# INPUT.net
KiCad netlist of a schematic drawn in EAGLE
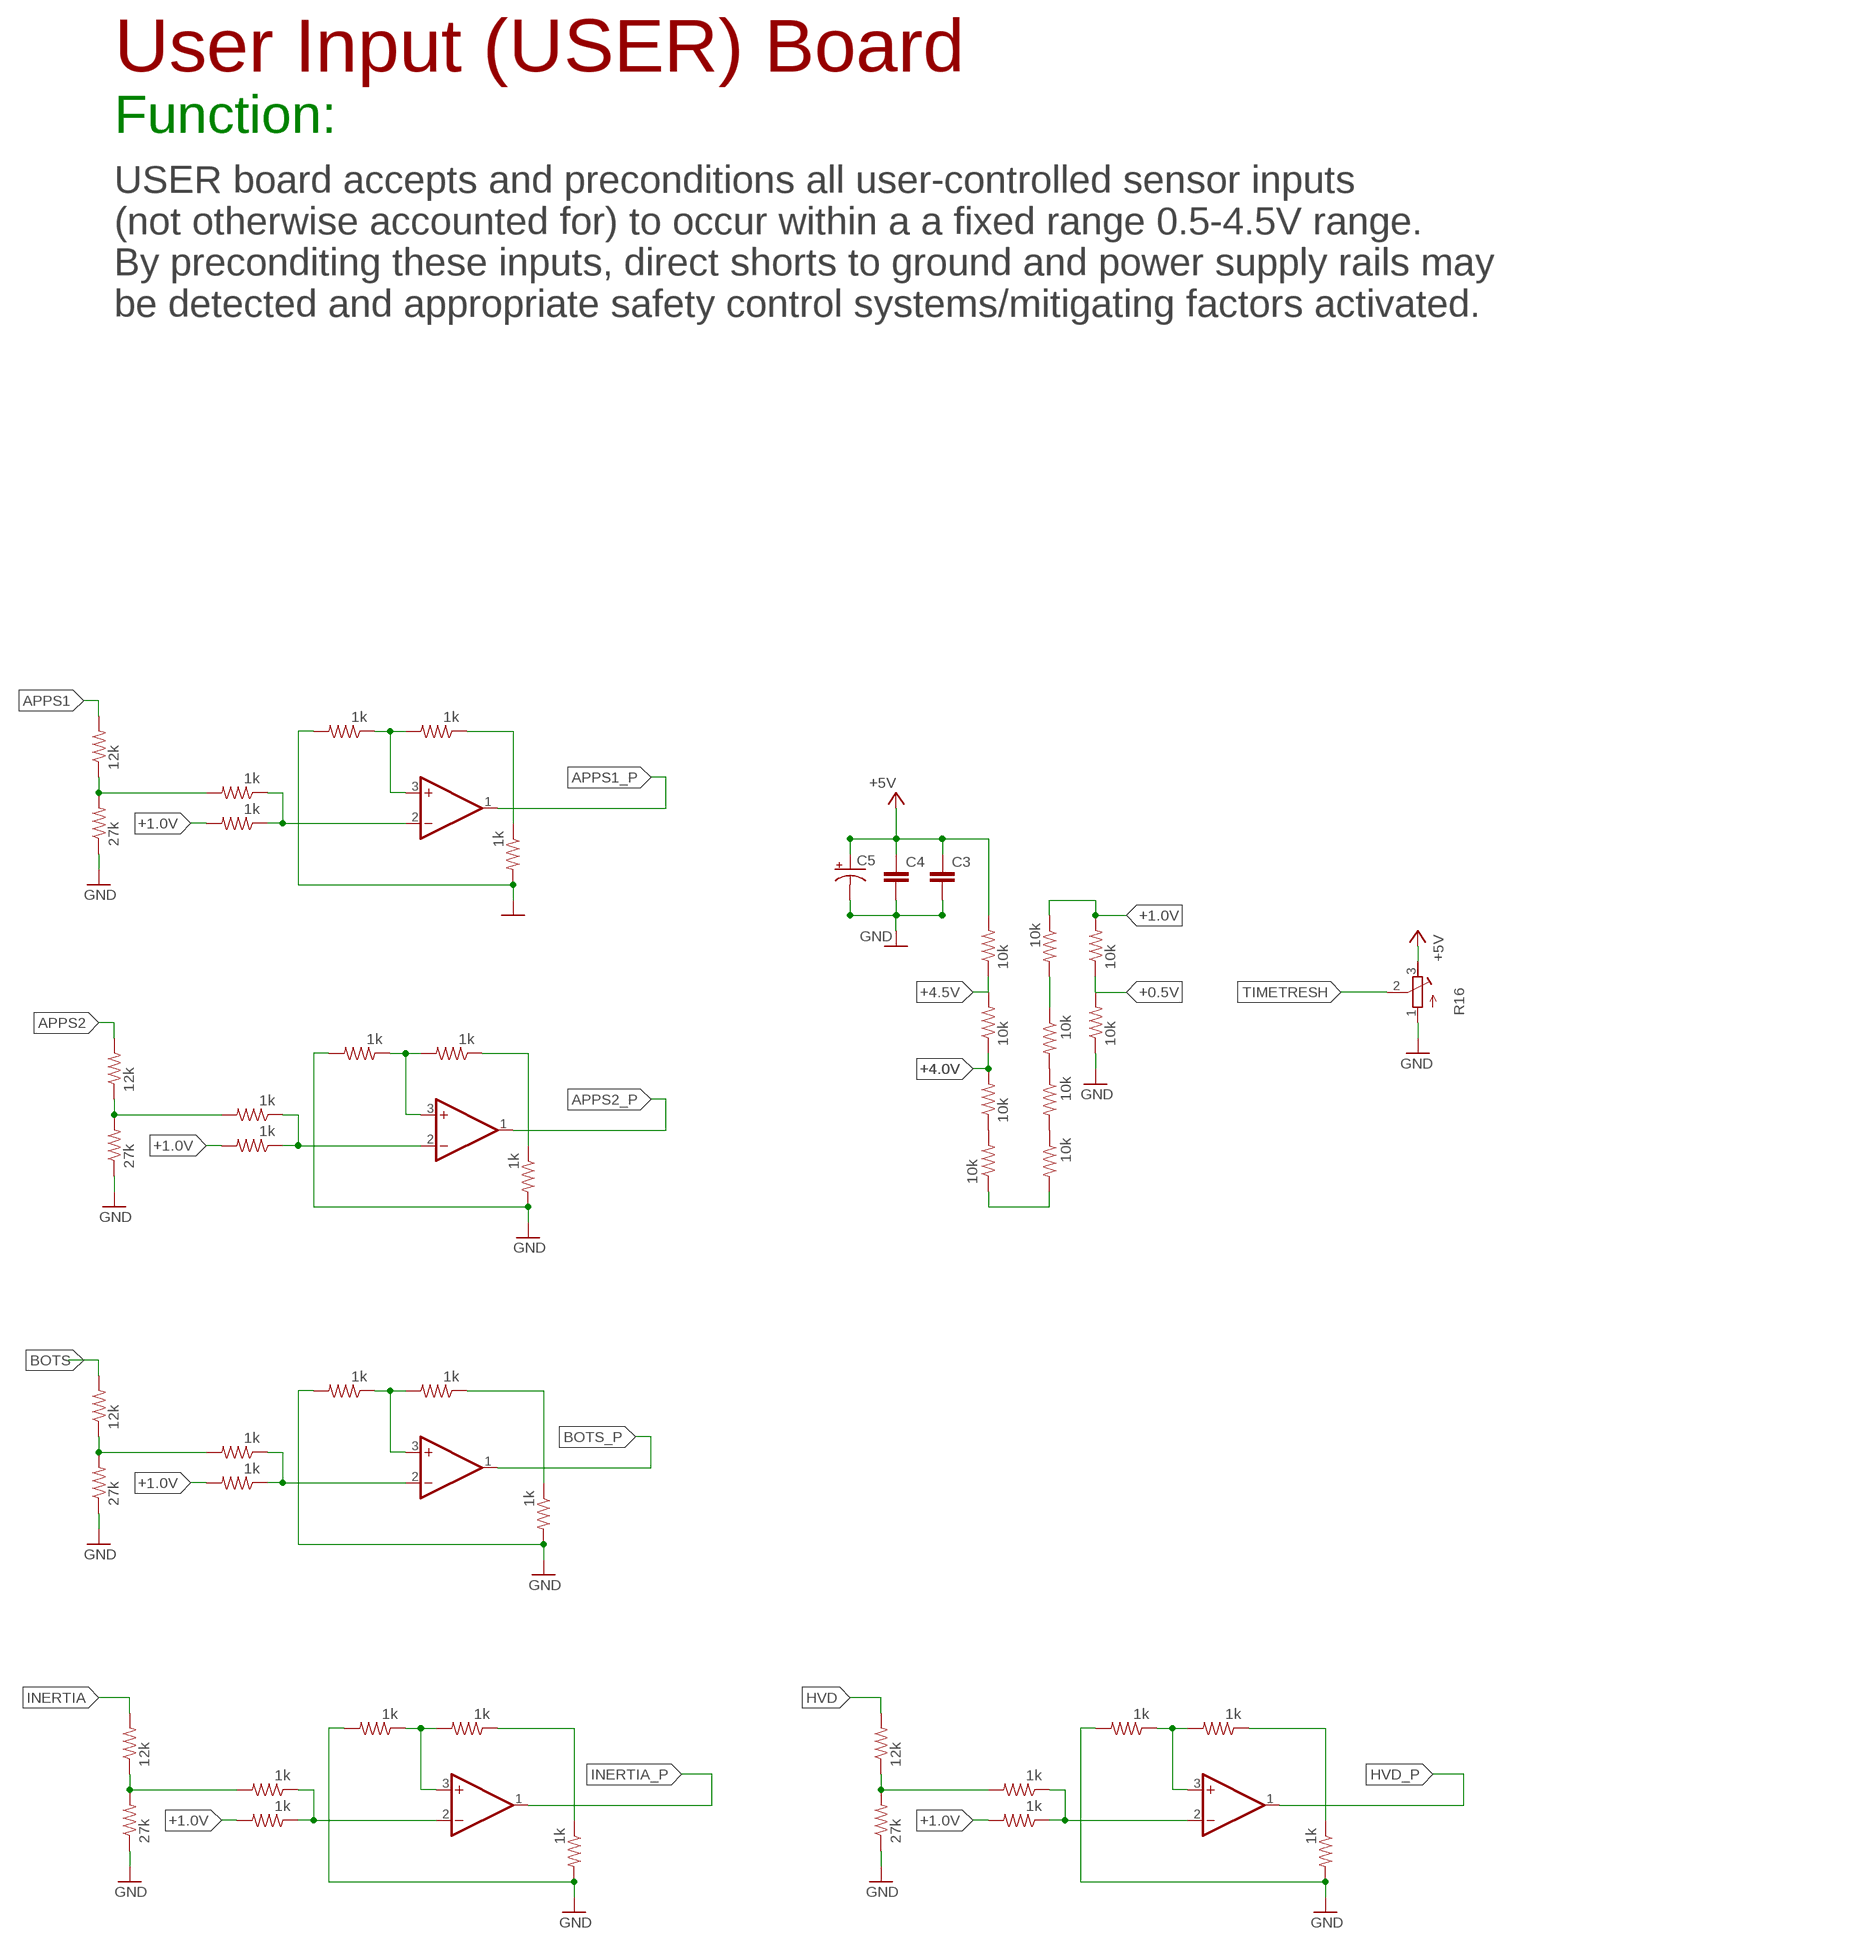
[diagram p0: schematic, sheet 1, part 1 of 2]
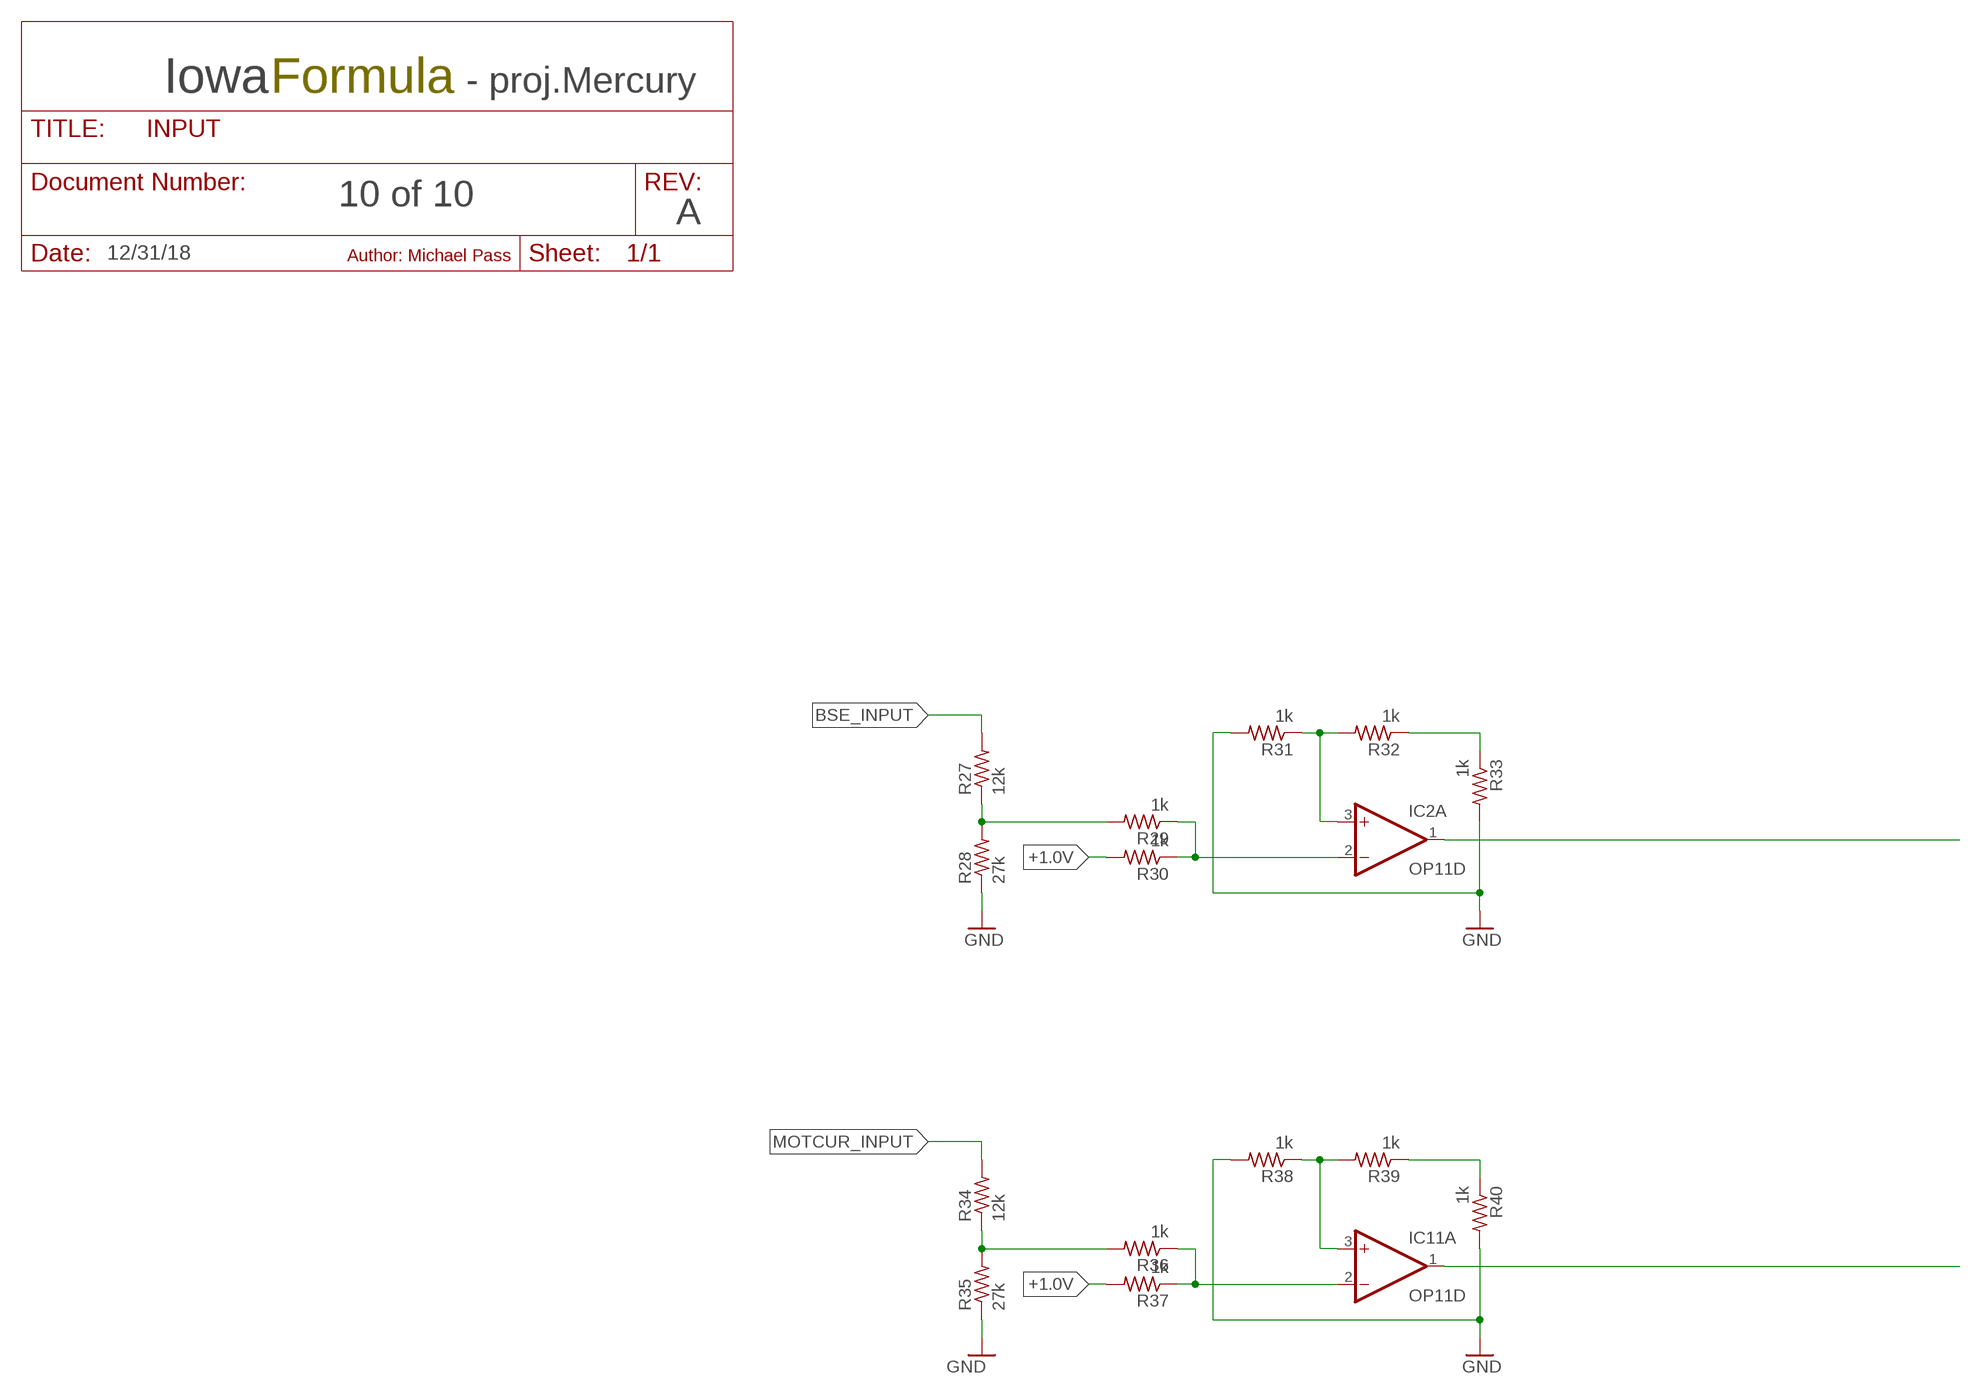
[diagram p1: schematic, sheet 1, part 2 of 2]

(export (version "E")
  (design (tool "Eeschema 10.0.6"))
  (components
    (comp (ref "C3")
      (value "C-EUC0805")
      (footprint "eagle-import:C0805")
      (libsource (lib "eagle-import") (part "C-EUC0805"))
    )
    (comp (ref "C4")
      (value "C-EUC0805")
      (footprint "eagle-import:C0805")
      (libsource (lib "eagle-import") (part "C-EUC0805"))
    )
    (comp (ref "C5")
      (value "CPOL-US085CS-1AR")
      (footprint "eagle-import:085CS_1AR")
      (libsource (lib "eagle-import") (part "CPOL-US085CS-1AR"))
    )
    (comp (ref "IC2")
      (value "OP11D")
      (footprint "eagle-import:SO14")
      (libsource (lib "eagle-import") (part "OP11D"))
    )
    (comp (ref "IC3")
      (value "OP11D")
      (footprint "eagle-import:SO14")
      (libsource (lib "eagle-import") (part "OP11D"))
    )
    (comp (ref "IC7")
      (value "OP11D")
      (footprint "eagle-import:SO14")
      (libsource (lib "eagle-import") (part "OP11D"))
    )
    (comp (ref "IC8")
      (value "OP11D")
      (footprint "eagle-import:SO14")
      (libsource (lib "eagle-import") (part "OP11D"))
    )
    (comp (ref "IC11")
      (value "OP11D")
      (footprint "eagle-import:SO14")
      (libsource (lib "eagle-import") (part "OP11D"))
    )
    (comp (ref "IC19")
      (value "OP11D")
      (footprint "eagle-import:SO14")
      (libsource (lib "eagle-import") (part "OP11D"))
    )
    (comp (ref "IC20")
      (value "OP11D")
      (footprint "eagle-import:SO14")
      (libsource (lib "eagle-import") (part "OP11D"))
    )
    (comp (ref "R1")
      (value "12k")
      (footprint "eagle-import:R0805")
      (libsource (lib "eagle-import") (part "R-US_R0805"))
    )
    (comp (ref "R2")
      (value "27k")
      (footprint "eagle-import:R0805")
      (libsource (lib "eagle-import") (part "R-US_R0805"))
    )
    (comp (ref "R5")
      (value "10k")
      (footprint "eagle-import:R0805")
      (libsource (lib "eagle-import") (part "R-US_R0805"))
    )
    (comp (ref "R6")
      (value "10k")
      (footprint "eagle-import:R0805")
      (libsource (lib "eagle-import") (part "R-US_R0805"))
    )
    (comp (ref "R7")
      (value "12k")
      (footprint "eagle-import:R0805")
      (libsource (lib "eagle-import") (part "R-US_R0805"))
    )
    (comp (ref "R8")
      (value "10k")
      (footprint "eagle-import:R0805")
      (libsource (lib "eagle-import") (part "R-US_R0805"))
    )
    (comp (ref "R9")
      (value "10k")
      (footprint "eagle-import:R0805")
      (libsource (lib "eagle-import") (part "R-US_R0805"))
    )
    (comp (ref "R10")
      (value "10k")
      (footprint "eagle-import:R0805")
      (libsource (lib "eagle-import") (part "R-US_R0805"))
    )
    (comp (ref "R11")
      (value "10k")
      (footprint "eagle-import:R0805")
      (libsource (lib "eagle-import") (part "R-US_R0805"))
    )
    (comp (ref "R12")
      (value "10k")
      (footprint "eagle-import:R0805")
      (libsource (lib "eagle-import") (part "R-US_R0805"))
    )
    (comp (ref "R13")
      (value "10k")
      (footprint "eagle-import:R0805")
      (libsource (lib "eagle-import") (part "R-US_R0805"))
    )
    (comp (ref "R14")
      (value "10k")
      (footprint "eagle-import:R0805")
      (libsource (lib "eagle-import") (part "R-US_R0805"))
    )
    (comp (ref "R15")
      (value "10k")
      (footprint "eagle-import:R0805")
      (libsource (lib "eagle-import") (part "R-US_R0805"))
    )
    (comp (ref "R16")
      (value "R-TRIMM3224X")
      (footprint "eagle-import:RTRIM3224X")
      (libsource (lib "eagle-import") (part "R-TRIMM3224X"))
    )
    (comp (ref "R21")
      (value "27k")
      (footprint "eagle-import:R0805")
      (libsource (lib "eagle-import") (part "R-US_R0805"))
    )
    (comp (ref "R22")
      (value "1k")
      (footprint "eagle-import:R0805")
      (libsource (lib "eagle-import") (part "R-US_R0805"))
    )
    (comp (ref "R23")
      (value "1k")
      (footprint "eagle-import:R0805")
      (libsource (lib "eagle-import") (part "R-US_R0805"))
    )
    (comp (ref "R24")
      (value "1k")
      (footprint "eagle-import:R0805")
      (libsource (lib "eagle-import") (part "R-US_R0805"))
    )
    (comp (ref "R25")
      (value "1k")
      (footprint "eagle-import:R0805")
      (libsource (lib "eagle-import") (part "R-US_R0805"))
    )
    (comp (ref "R26")
      (value "1k")
      (footprint "eagle-import:R0805")
      (libsource (lib "eagle-import") (part "R-US_R0805"))
    )
    (comp (ref "R27")
      (value "12k")
      (footprint "eagle-import:R0805")
      (libsource (lib "eagle-import") (part "R-US_R0805"))
    )
    (comp (ref "R28")
      (value "27k")
      (footprint "eagle-import:R0805")
      (libsource (lib "eagle-import") (part "R-US_R0805"))
    )
    (comp (ref "R29")
      (value "1k")
      (footprint "eagle-import:R0805")
      (libsource (lib "eagle-import") (part "R-US_R0805"))
    )
    (comp (ref "R30")
      (value "1k")
      (footprint "eagle-import:R0805")
      (libsource (lib "eagle-import") (part "R-US_R0805"))
    )
    (comp (ref "R31")
      (value "1k")
      (footprint "eagle-import:R0805")
      (libsource (lib "eagle-import") (part "R-US_R0805"))
    )
    (comp (ref "R32")
      (value "1k")
      (footprint "eagle-import:R0805")
      (libsource (lib "eagle-import") (part "R-US_R0805"))
    )
    (comp (ref "R33")
      (value "1k")
      (footprint "eagle-import:R0805")
      (libsource (lib "eagle-import") (part "R-US_R0805"))
    )
    (comp (ref "R34")
      (value "12k")
      (footprint "eagle-import:R0805")
      (libsource (lib "eagle-import") (part "R-US_R0805"))
    )
    (comp (ref "R35")
      (value "27k")
      (footprint "eagle-import:R0805")
      (libsource (lib "eagle-import") (part "R-US_R0805"))
    )
    (comp (ref "R36")
      (value "1k")
      (footprint "eagle-import:R0805")
      (libsource (lib "eagle-import") (part "R-US_R0805"))
    )
    (comp (ref "R37")
      (value "1k")
      (footprint "eagle-import:R0805")
      (libsource (lib "eagle-import") (part "R-US_R0805"))
    )
    (comp (ref "R38")
      (value "1k")
      (footprint "eagle-import:R0805")
      (libsource (lib "eagle-import") (part "R-US_R0805"))
    )
    (comp (ref "R39")
      (value "1k")
      (footprint "eagle-import:R0805")
      (libsource (lib "eagle-import") (part "R-US_R0805"))
    )
    (comp (ref "R40")
      (value "1k")
      (footprint "eagle-import:R0805")
      (libsource (lib "eagle-import") (part "R-US_R0805"))
    )
    (comp (ref "R66")
      (value "1k")
      (footprint "eagle-import:R0805")
      (libsource (lib "eagle-import") (part "R-US_R0805"))
    )
    (comp (ref "R67")
      (value "1k")
      (footprint "eagle-import:R0805")
      (libsource (lib "eagle-import") (part "R-US_R0805"))
    )
    (comp (ref "R68")
      (value "1k")
      (footprint "eagle-import:R0805")
      (libsource (lib "eagle-import") (part "R-US_R0805"))
    )
    (comp (ref "R69")
      (value "1k")
      (footprint "eagle-import:R0805")
      (libsource (lib "eagle-import") (part "R-US_R0805"))
    )
    (comp (ref "R70")
      (value "1k")
      (footprint "eagle-import:R0805")
      (libsource (lib "eagle-import") (part "R-US_R0805"))
    )
    (comp (ref "R71")
      (value "12k")
      (footprint "eagle-import:R0805")
      (libsource (lib "eagle-import") (part "R-US_R0805"))
    )
    (comp (ref "R72")
      (value "27k")
      (footprint "eagle-import:R0805")
      (libsource (lib "eagle-import") (part "R-US_R0805"))
    )
    (comp (ref "R73")
      (value "1k")
      (footprint "eagle-import:R0805")
      (libsource (lib "eagle-import") (part "R-US_R0805"))
    )
    (comp (ref "R74")
      (value "1k")
      (footprint "eagle-import:R0805")
      (libsource (lib "eagle-import") (part "R-US_R0805"))
    )
    (comp (ref "R75")
      (value "1k")
      (footprint "eagle-import:R0805")
      (libsource (lib "eagle-import") (part "R-US_R0805"))
    )
    (comp (ref "R76")
      (value "1k")
      (footprint "eagle-import:R0805")
      (libsource (lib "eagle-import") (part "R-US_R0805"))
    )
    (comp (ref "R77")
      (value "1k")
      (footprint "eagle-import:R0805")
      (libsource (lib "eagle-import") (part "R-US_R0805"))
    )
    (comp (ref "R78")
      (value "12k")
      (footprint "eagle-import:R0805")
      (libsource (lib "eagle-import") (part "R-US_R0805"))
    )
    (comp (ref "R79")
      (value "27k")
      (footprint "eagle-import:R0805")
      (libsource (lib "eagle-import") (part "R-US_R0805"))
    )
    (comp (ref "R80")
      (value "1k")
      (footprint "eagle-import:R0805")
      (libsource (lib "eagle-import") (part "R-US_R0805"))
    )
    (comp (ref "R81")
      (value "1k")
      (footprint "eagle-import:R0805")
      (libsource (lib "eagle-import") (part "R-US_R0805"))
    )
    (comp (ref "R82")
      (value "1k")
      (footprint "eagle-import:R0805")
      (libsource (lib "eagle-import") (part "R-US_R0805"))
    )
    (comp (ref "R83")
      (value "1k")
      (footprint "eagle-import:R0805")
      (libsource (lib "eagle-import") (part "R-US_R0805"))
    )
    (comp (ref "R84")
      (value "1k")
      (footprint "eagle-import:R0805")
      (libsource (lib "eagle-import") (part "R-US_R0805"))
    )
    (comp (ref "R85")
      (value "12k")
      (footprint "eagle-import:R0805")
      (libsource (lib "eagle-import") (part "R-US_R0805"))
    )
    (comp (ref "R86")
      (value "27k")
      (footprint "eagle-import:R0805")
      (libsource (lib "eagle-import") (part "R-US_R0805"))
    )
    (comp (ref "R87")
      (value "1k")
      (footprint "eagle-import:R0805")
      (libsource (lib "eagle-import") (part "R-US_R0805"))
    )
    (comp (ref "R88")
      (value "1k")
      (footprint "eagle-import:R0805")
      (libsource (lib "eagle-import") (part "R-US_R0805"))
    )
    (comp (ref "R89")
      (value "1k")
      (footprint "eagle-import:R0805")
      (libsource (lib "eagle-import") (part "R-US_R0805"))
    )
    (comp (ref "R90")
      (value "1k")
      (footprint "eagle-import:R0805")
      (libsource (lib "eagle-import") (part "R-US_R0805"))
    )
    (comp (ref "R91")
      (value "1k")
      (footprint "eagle-import:R0805")
      (libsource (lib "eagle-import") (part "R-US_R0805"))
    )
  )
  (nets
    (net (code "1") (name "+0.5V") (class "Default")
      (node (ref "R14") (pin "1") (pinfunction "1_1") (pintype "passive"))
      (node (ref "R15") (pin "2") (pinfunction "2_2") (pintype "passive"))
    )
    (net (code "2") (name "+1.0V") (class "Default")
      (node (ref "R13") (pin "1") (pinfunction "1_1") (pintype "passive"))
      (node (ref "R14") (pin "2") (pinfunction "2_2") (pintype "passive"))
      (node (ref "R23") (pin "2") (pinfunction "2_2") (pintype "passive"))
      (node (ref "R30") (pin "2") (pinfunction "2_2") (pintype "passive"))
      (node (ref "R37") (pin "2") (pinfunction "2_2") (pintype "passive"))
      (node (ref "R67") (pin "2") (pinfunction "2_2") (pintype "passive"))
      (node (ref "R74") (pin "2") (pinfunction "2_2") (pintype "passive"))
      (node (ref "R81") (pin "2") (pinfunction "2_2") (pintype "passive"))
      (node (ref "R88") (pin "2") (pinfunction "2_2") (pintype "passive"))
    )
    (net (code "3") (name "+4.0V") (class "Default")
      (node (ref "R6") (pin "1") (pinfunction "1_1") (pintype "passive"))
      (node (ref "R8") (pin "2") (pinfunction "2_2") (pintype "passive"))
    )
    (net (code "4") (name "+4.5V") (class "Default")
      (node (ref "R5") (pin "1") (pinfunction "1_1") (pintype "passive"))
      (node (ref "R6") (pin "2") (pinfunction "2_2") (pintype "passive"))
    )
    (net (code "5") (name "+5V") (class "Default")
      (node (ref "C3") (pin "1") (pinfunction "1_1") (pintype "passive"))
      (node (ref "C4") (pin "1") (pinfunction "1_1") (pintype "passive"))
      (node (ref "C5") (pin "+") (pinfunction "+_+") (pintype "passive"))
      (node (ref "R16") (pin "3") (pinfunction "E_3") (pintype "passive"))
      (node (ref "R5") (pin "2") (pinfunction "2_2") (pintype "passive"))
    )
    (net (code "6") (name "APPS1") (class "Default")
      (node (ref "R71") (pin "2") (pinfunction "2_2") (pintype "passive"))
    )
    (net (code "7") (name "APPS1_P") (class "Default")
      (node (ref "IC7") (pin "1") (pinfunction "OUT_1") (pintype "output"))
    )
    (net (code "8") (name "APPS2") (class "Default")
      (node (ref "R78") (pin "2") (pinfunction "2_2") (pintype "passive"))
    )
    (net (code "9") (name "APPS2_P") (class "Default")
      (node (ref "IC19") (pin "1") (pinfunction "OUT_1") (pintype "output"))
    )
    (net (code "10") (name "BOTS") (class "Default")
      (node (ref "R7") (pin "2") (pinfunction "2_2") (pintype "passive"))
    )
    (net (code "11") (name "BOTS_P") (class "Default")
      (node (ref "IC8") (pin "1") (pinfunction "OUT_1") (pintype "output"))
    )
    (net (code "12") (name "BSE_INPUT") (class "Default")
      (node (ref "R27") (pin "2") (pinfunction "2_2") (pintype "passive"))
    )
    (net (code "13") (name "GND") (class "Default")
      (node (ref "C3") (pin "2") (pinfunction "2_2") (pintype "passive"))
      (node (ref "C4") (pin "2") (pinfunction "2_2") (pintype "passive"))
      (node (ref "C5") (pin "-") (pinfunction "-_-") (pintype "passive"))
      (node (ref "R15") (pin "1") (pinfunction "1_1") (pintype "passive"))
      (node (ref "R16") (pin "1") (pinfunction "A_1") (pintype "passive"))
      (node (ref "R2") (pin "1") (pinfunction "1_1") (pintype "passive"))
      (node (ref "R21") (pin "1") (pinfunction "1_1") (pintype "passive"))
      (node (ref "R24") (pin "2") (pinfunction "2_2") (pintype "passive"))
      (node (ref "R26") (pin "2") (pinfunction "2_2") (pintype "passive"))
      (node (ref "R28") (pin "1") (pinfunction "1_1") (pintype "passive"))
      (node (ref "R31") (pin "2") (pinfunction "2_2") (pintype "passive"))
      (node (ref "R33") (pin "2") (pinfunction "2_2") (pintype "passive"))
      (node (ref "R35") (pin "1") (pinfunction "1_1") (pintype "passive"))
      (node (ref "R38") (pin "2") (pinfunction "2_2") (pintype "passive"))
      (node (ref "R40") (pin "2") (pinfunction "2_2") (pintype "passive"))
      (node (ref "R68") (pin "2") (pinfunction "2_2") (pintype "passive"))
      (node (ref "R70") (pin "2") (pinfunction "2_2") (pintype "passive"))
      (node (ref "R72") (pin "1") (pinfunction "1_1") (pintype "passive"))
      (node (ref "R75") (pin "2") (pinfunction "2_2") (pintype "passive"))
      (node (ref "R77") (pin "2") (pinfunction "2_2") (pintype "passive"))
      (node (ref "R79") (pin "1") (pinfunction "1_1") (pintype "passive"))
      (node (ref "R82") (pin "2") (pinfunction "2_2") (pintype "passive"))
      (node (ref "R84") (pin "2") (pinfunction "2_2") (pintype "passive"))
      (node (ref "R86") (pin "1") (pinfunction "1_1") (pintype "passive"))
      (node (ref "R89") (pin "2") (pinfunction "2_2") (pintype "passive"))
      (node (ref "R91") (pin "2") (pinfunction "2_2") (pintype "passive"))
    )
    (net (code "14") (name "HVD") (class "Default")
      (node (ref "R85") (pin "2") (pinfunction "2_2") (pintype "passive"))
    )
    (net (code "15") (name "HVD_P") (class "Default")
      (node (ref "IC20") (pin "1") (pinfunction "OUT_1") (pintype "output"))
    )
    (net (code "16") (name "INERTIA") (class "Default")
      (node (ref "R1") (pin "2") (pinfunction "2_2") (pintype "passive"))
    )
    (net (code "17") (name "INERTIA_P") (class "Default")
      (node (ref "IC3") (pin "1") (pinfunction "OUT_1") (pintype "output"))
    )
    (net (code "18") (name "MOTCUR_INPUT") (class "Default")
      (node (ref "R34") (pin "2") (pinfunction "2_2") (pintype "passive"))
    )
    (net (code "19") (name "Net-(IC2A-+IN)") (class "Default")
      (node (ref "IC2") (pin "3") (pinfunction "+IN_3") (pintype "input"))
      (node (ref "R31") (pin "1") (pinfunction "1_1") (pintype "passive"))
      (node (ref "R32") (pin "2") (pinfunction "2_2") (pintype "passive"))
    )
    (net (code "20") (name "Net-(IC2A--IN)") (class "Default")
      (node (ref "IC2") (pin "2") (pinfunction "-IN_2") (pintype "input"))
      (node (ref "R29") (pin "1") (pinfunction "1_1") (pintype "passive"))
      (node (ref "R30") (pin "1") (pinfunction "1_1") (pintype "passive"))
    )
    (net (code "21") (name "Net-(IC3A-+IN)") (class "Default")
      (node (ref "IC3") (pin "3") (pinfunction "+IN_3") (pintype "input"))
      (node (ref "R68") (pin "1") (pinfunction "1_1") (pintype "passive"))
      (node (ref "R69") (pin "2") (pinfunction "2_2") (pintype "passive"))
    )
    (net (code "22") (name "Net-(IC3A--IN)") (class "Default")
      (node (ref "IC3") (pin "2") (pinfunction "-IN_2") (pintype "input"))
      (node (ref "R66") (pin "1") (pinfunction "1_1") (pintype "passive"))
      (node (ref "R67") (pin "1") (pinfunction "1_1") (pintype "passive"))
    )
    (net (code "23") (name "Net-(IC7A-+IN)") (class "Default")
      (node (ref "IC7") (pin "3") (pinfunction "+IN_3") (pintype "input"))
      (node (ref "R75") (pin "1") (pinfunction "1_1") (pintype "passive"))
      (node (ref "R76") (pin "2") (pinfunction "2_2") (pintype "passive"))
    )
    (net (code "24") (name "Net-(IC7A--IN)") (class "Default")
      (node (ref "IC7") (pin "2") (pinfunction "-IN_2") (pintype "input"))
      (node (ref "R73") (pin "1") (pinfunction "1_1") (pintype "passive"))
      (node (ref "R74") (pin "1") (pinfunction "1_1") (pintype "passive"))
    )
    (net (code "25") (name "Net-(IC8A-+IN)") (class "Default")
      (node (ref "IC8") (pin "3") (pinfunction "+IN_3") (pintype "input"))
      (node (ref "R24") (pin "1") (pinfunction "1_1") (pintype "passive"))
      (node (ref "R25") (pin "2") (pinfunction "2_2") (pintype "passive"))
    )
    (net (code "26") (name "Net-(IC8A--IN)") (class "Default")
      (node (ref "IC8") (pin "2") (pinfunction "-IN_2") (pintype "input"))
      (node (ref "R22") (pin "1") (pinfunction "1_1") (pintype "passive"))
      (node (ref "R23") (pin "1") (pinfunction "1_1") (pintype "passive"))
    )
    (net (code "27") (name "Net-(IC11A-+IN)") (class "Default")
      (node (ref "IC11") (pin "3") (pinfunction "+IN_3") (pintype "input"))
      (node (ref "R38") (pin "1") (pinfunction "1_1") (pintype "passive"))
      (node (ref "R39") (pin "2") (pinfunction "2_2") (pintype "passive"))
    )
    (net (code "28") (name "Net-(IC11A--IN)") (class "Default")
      (node (ref "IC11") (pin "2") (pinfunction "-IN_2") (pintype "input"))
      (node (ref "R36") (pin "1") (pinfunction "1_1") (pintype "passive"))
      (node (ref "R37") (pin "1") (pinfunction "1_1") (pintype "passive"))
    )
    (net (code "29") (name "Net-(IC19A-+IN)") (class "Default")
      (node (ref "IC19") (pin "3") (pinfunction "+IN_3") (pintype "input"))
      (node (ref "R82") (pin "1") (pinfunction "1_1") (pintype "passive"))
      (node (ref "R83") (pin "2") (pinfunction "2_2") (pintype "passive"))
    )
    (net (code "30") (name "Net-(IC19A--IN)") (class "Default")
      (node (ref "IC19") (pin "2") (pinfunction "-IN_2") (pintype "input"))
      (node (ref "R80") (pin "1") (pinfunction "1_1") (pintype "passive"))
      (node (ref "R81") (pin "1") (pinfunction "1_1") (pintype "passive"))
    )
    (net (code "31") (name "Net-(IC20A-+IN)") (class "Default")
      (node (ref "IC20") (pin "3") (pinfunction "+IN_3") (pintype "input"))
      (node (ref "R89") (pin "1") (pinfunction "1_1") (pintype "passive"))
      (node (ref "R90") (pin "2") (pinfunction "2_2") (pintype "passive"))
    )
    (net (code "32") (name "Net-(IC20A--IN)") (class "Default")
      (node (ref "IC20") (pin "2") (pinfunction "-IN_2") (pintype "input"))
      (node (ref "R87") (pin "1") (pinfunction "1_1") (pintype "passive"))
      (node (ref "R88") (pin "1") (pinfunction "1_1") (pintype "passive"))
    )
    (net (code "33") (name "Net-(R1-Pad1)") (class "Default")
      (node (ref "R1") (pin "1") (pinfunction "1_1") (pintype "passive"))
      (node (ref "R2") (pin "2") (pinfunction "2_2") (pintype "passive"))
      (node (ref "R66") (pin "2") (pinfunction "2_2") (pintype "passive"))
    )
    (net (code "34") (name "Net-(R8-Pad1)") (class "Default")
      (node (ref "R8") (pin "1") (pinfunction "1_1") (pintype "passive"))
      (node (ref "R9") (pin "2") (pinfunction "2_2") (pintype "passive"))
    )
    (net (code "35") (name "Net-(R10-Pad1)") (class "Default")
      (node (ref "R10") (pin "1") (pinfunction "1_1") (pintype "passive"))
      (node (ref "R11") (pin "2") (pinfunction "2_2") (pintype "passive"))
    )
    (net (code "36") (name "Net-(R10-Pad2)") (class "Default")
      (node (ref "R10") (pin "2") (pinfunction "2_2") (pintype "passive"))
      (node (ref "R9") (pin "1") (pinfunction "1_1") (pintype "passive"))
    )
    (net (code "37") (name "Net-(R11-Pad1)") (class "Default")
      (node (ref "R11") (pin "1") (pinfunction "1_1") (pintype "passive"))
      (node (ref "R12") (pin "2") (pinfunction "2_2") (pintype "passive"))
    )
    (net (code "38") (name "Net-(R12-Pad1)") (class "Default")
      (node (ref "R12") (pin "1") (pinfunction "1_1") (pintype "passive"))
      (node (ref "R13") (pin "2") (pinfunction "2_2") (pintype "passive"))
    )
    (net (code "39") (name "Net-(R21-Pad2)") (class "Default")
      (node (ref "R21") (pin "2") (pinfunction "2_2") (pintype "passive"))
      (node (ref "R22") (pin "2") (pinfunction "2_2") (pintype "passive"))
      (node (ref "R7") (pin "1") (pinfunction "1_1") (pintype "passive"))
    )
    (net (code "40") (name "Net-(R25-Pad1)") (class "Default")
      (node (ref "R25") (pin "1") (pinfunction "1_1") (pintype "passive"))
      (node (ref "R26") (pin "1") (pinfunction "1_1") (pintype "passive"))
    )
    (net (code "41") (name "Net-(R27-Pad1)") (class "Default")
      (node (ref "R27") (pin "1") (pinfunction "1_1") (pintype "passive"))
      (node (ref "R28") (pin "2") (pinfunction "2_2") (pintype "passive"))
      (node (ref "R29") (pin "2") (pinfunction "2_2") (pintype "passive"))
    )
    (net (code "42") (name "Net-(R32-Pad1)") (class "Default")
      (node (ref "R32") (pin "1") (pinfunction "1_1") (pintype "passive"))
      (node (ref "R33") (pin "1") (pinfunction "1_1") (pintype "passive"))
    )
    (net (code "43") (name "Net-(R34-Pad1)") (class "Default")
      (node (ref "R34") (pin "1") (pinfunction "1_1") (pintype "passive"))
      (node (ref "R35") (pin "2") (pinfunction "2_2") (pintype "passive"))
      (node (ref "R36") (pin "2") (pinfunction "2_2") (pintype "passive"))
    )
    (net (code "44") (name "Net-(R39-Pad1)") (class "Default")
      (node (ref "R39") (pin "1") (pinfunction "1_1") (pintype "passive"))
      (node (ref "R40") (pin "1") (pinfunction "1_1") (pintype "passive"))
    )
    (net (code "45") (name "Net-(R69-Pad1)") (class "Default")
      (node (ref "R69") (pin "1") (pinfunction "1_1") (pintype "passive"))
      (node (ref "R70") (pin "1") (pinfunction "1_1") (pintype "passive"))
    )
    (net (code "46") (name "Net-(R71-Pad1)") (class "Default")
      (node (ref "R71") (pin "1") (pinfunction "1_1") (pintype "passive"))
      (node (ref "R72") (pin "2") (pinfunction "2_2") (pintype "passive"))
      (node (ref "R73") (pin "2") (pinfunction "2_2") (pintype "passive"))
    )
    (net (code "47") (name "Net-(R76-Pad1)") (class "Default")
      (node (ref "R76") (pin "1") (pinfunction "1_1") (pintype "passive"))
      (node (ref "R77") (pin "1") (pinfunction "1_1") (pintype "passive"))
    )
    (net (code "48") (name "Net-(R78-Pad1)") (class "Default")
      (node (ref "R78") (pin "1") (pinfunction "1_1") (pintype "passive"))
      (node (ref "R79") (pin "2") (pinfunction "2_2") (pintype "passive"))
      (node (ref "R80") (pin "2") (pinfunction "2_2") (pintype "passive"))
    )
    (net (code "49") (name "Net-(R83-Pad1)") (class "Default")
      (node (ref "R83") (pin "1") (pinfunction "1_1") (pintype "passive"))
      (node (ref "R84") (pin "1") (pinfunction "1_1") (pintype "passive"))
    )
    (net (code "50") (name "Net-(R85-Pad1)") (class "Default")
      (node (ref "R85") (pin "1") (pinfunction "1_1") (pintype "passive"))
      (node (ref "R86") (pin "2") (pinfunction "2_2") (pintype "passive"))
      (node (ref "R87") (pin "2") (pinfunction "2_2") (pintype "passive"))
    )
    (net (code "51") (name "Net-(R90-Pad1)") (class "Default")
      (node (ref "R90") (pin "1") (pinfunction "1_1") (pintype "passive"))
      (node (ref "R91") (pin "1") (pinfunction "1_1") (pintype "passive"))
    )
    (net (code "52") (name "TIMETRESH") (class "Default")
      (node (ref "R16") (pin "2") (pinfunction "S_2") (pintype "passive"))
    )
    (net (code "53") (name "unconnected-(IC2A-OUT-Pad1)") (class "Default")
      (node (ref "IC2") (pin "1") (pinfunction "OUT_1") (pintype "output"))
    )
    (net (code "54") (name "unconnected-(IC11A-OUT-Pad1)") (class "Default")
      (node (ref "IC11") (pin "1") (pinfunction "OUT_1") (pintype "output"))
    )
  )
)
